# BUTTON_LED.net
KiCad netlist of a schematic drawn in Altium Designer
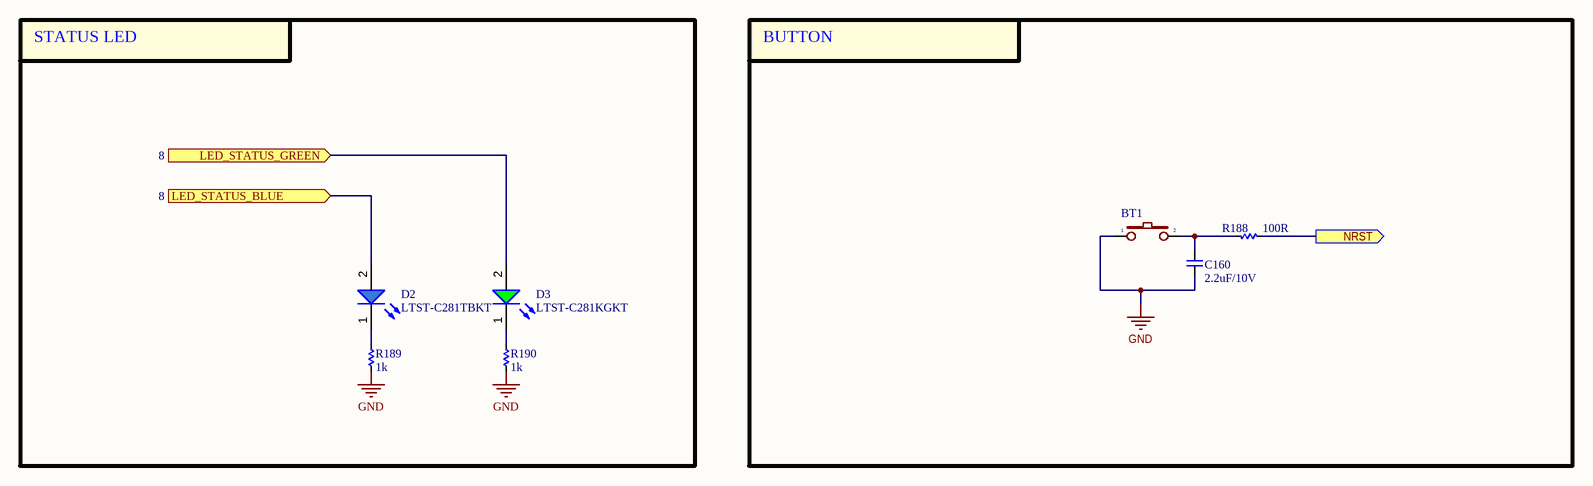
[diagram p0: BUTTON_LED.SchDoc]

(export (version "E")
  (design (tool "Eeschema 10.0.6"))
  (components
    (comp (ref "BT1")
      (value "BT_")
      (footprint "SW2-SMD")
      (description "Switch button 2 pin")
      (libsource (lib "IFBschelib") (part "BT2"))
    )
    (comp (ref "C160")
      (value "2.2uF/10V")
      (footprint "CAP_C_1005X50_L")
      (description "CAP CHIP")
      (libsource (lib "IFBschelib") (part "_CAP_C_2"))
    )
    (comp (ref "D2")
      (value "LTST-C281TBKT")
      (footprint "LED_0402")
      (libsource (lib "IFBschelib") (part "LED_BLUE"))
    )
    (comp (ref "D3")
      (value "LTST-C281KGKT")
      (footprint "LED_0402")
      (description "LED GREEN CLEAR 0402 SMD")
      (libsource (lib "IFBschelib") (part "LED_GREEN"))
    )
    (comp (ref "R188")
      (value "100R")
      (footprint "RES_C_1005x30_L")
      (description "RES")
      (libsource (lib "IFBschelib") (part "_RES_B_2"))
    )
    (comp (ref "R189")
      (value "1k")
      (footprint "RES_C_1005x30_L")
      (description "RES")
      (libsource (lib "IFBschelib") (part "_RES_B_2"))
    )
    (comp (ref "R190")
      (value "1k")
      (footprint "RES_C_1005x30_L")
      (description "RES")
      (libsource (lib "IFBschelib") (part "_RES_B_2"))
    )
  )
  (nets
    (net (code "1") (name "/LED_STATUS_BLUE") (class "Default")
      (node (ref "D2") (pin "2") (pinfunction "A_2") (pintype "passive"))
    )
    (net (code "2") (name "/LED_STATUS_GREEN") (class "Default")
      (node (ref "D3") (pin "2") (pinfunction "A_2") (pintype "passive"))
    )
    (net (code "3") (name "/NRST") (class "Default")
      (node (ref "R188") (pin "2") (pinfunction "2_2") (pintype "passive"))
    )
    (net (code "4") (name "GND") (class "Default")
      (node (ref "BT1") (pin "1") (pinfunction "1_1") (pintype "passive"))
      (node (ref "C160") (pin "1") (pinfunction "1_1") (pintype "passive"))
      (node (ref "R189") (pin "1") (pinfunction "1_1") (pintype "passive"))
      (node (ref "R190") (pin "1") (pinfunction "1_1") (pintype "passive"))
    )
    (net (code "5") (name "Net-(BT1-Pad2)") (class "Default")
      (node (ref "BT1") (pin "2") (pinfunction "2_2") (pintype "passive"))
      (node (ref "C160") (pin "2") (pinfunction "2_2") (pintype "passive"))
      (node (ref "R188") (pin "1") (pinfunction "1_1") (pintype "passive"))
    )
    (net (code "6") (name "Net-(D2-K)") (class "Default")
      (node (ref "D2") (pin "1") (pinfunction "K_1") (pintype "passive"))
      (node (ref "R189") (pin "2") (pinfunction "2_2") (pintype "passive"))
    )
    (net (code "7") (name "Net-(D3-K)") (class "Default")
      (node (ref "D3") (pin "1") (pinfunction "K_1") (pintype "passive"))
      (node (ref "R190") (pin "2") (pinfunction "2_2") (pintype "passive"))
    )
  )
)
